# FRA_daughter_v2.net
KiCad netlist of a schematic drawn in EAGLE
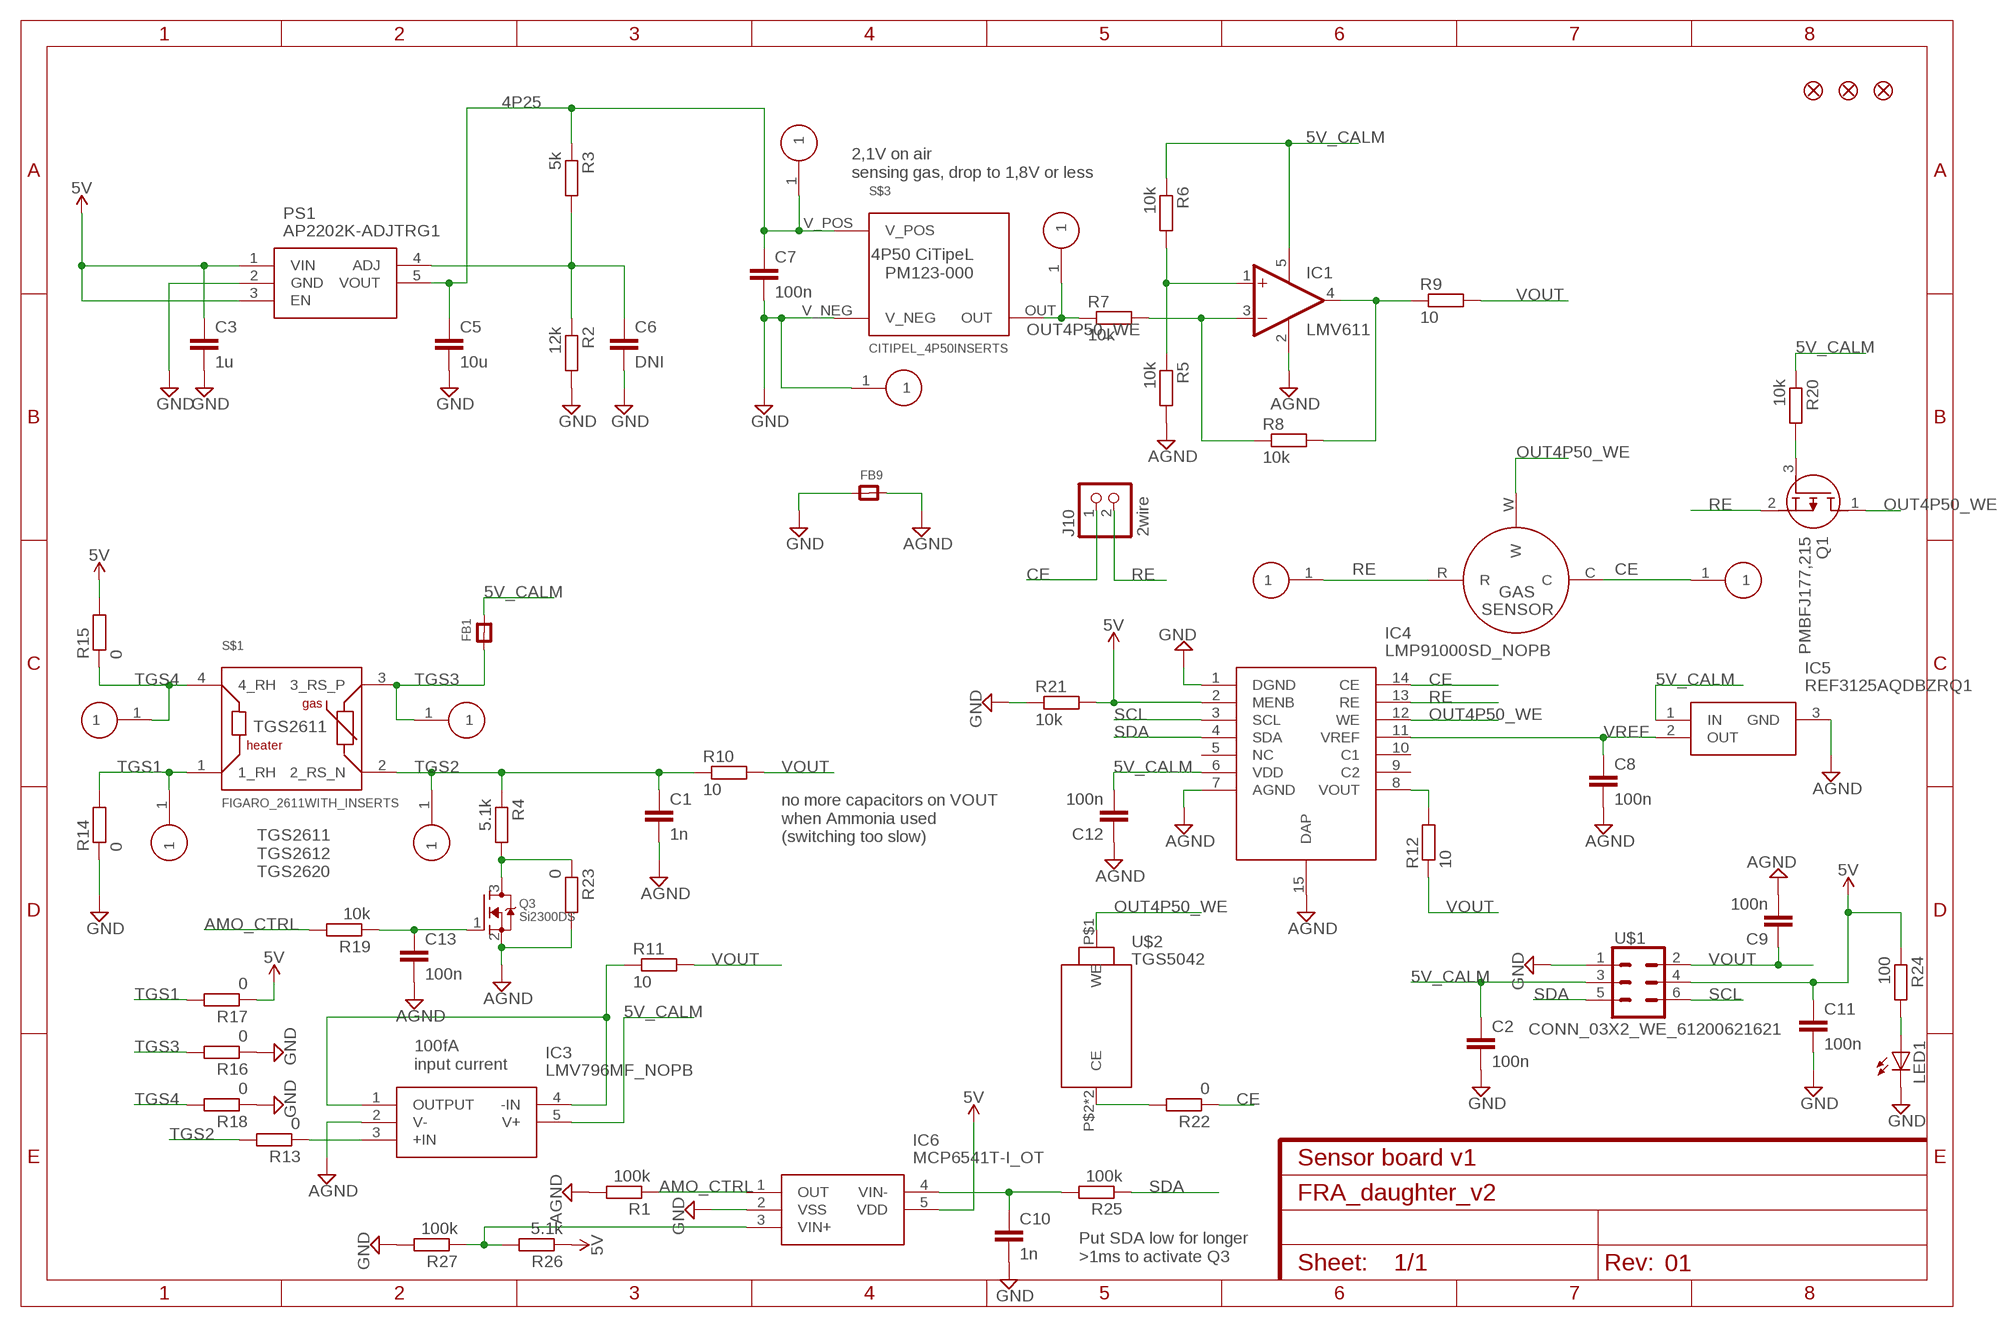
[diagram p0: schematic, sheet 1]

(export (version "E")
  (design (tool "Eeschema 10.0.6"))
  (components
    (comp (ref "C1")
      (value "1n")
      (footprint "eagle-import:C0603K")
      (libsource (lib "eagle-import") (part "C-EUC0603K"))
    )
    (comp (ref "C2")
      (value "100n")
      (footprint "eagle-import:C0603K")
      (libsource (lib "eagle-import") (part "C-EUC0603K"))
    )
    (comp (ref "C3")
      (value "1u")
      (footprint "eagle-import:C0603K")
      (libsource (lib "eagle-import") (part "C-EUC0603K"))
    )
    (comp (ref "C5")
      (value "10u")
      (footprint "eagle-import:C0603K")
      (libsource (lib "eagle-import") (part "C-EUC0603K"))
    )
    (comp (ref "C6")
      (value "DNI")
      (footprint "eagle-import:C0603K")
      (libsource (lib "eagle-import") (part "C-EUC0603K"))
    )
    (comp (ref "C7")
      (value "100n")
      (footprint "eagle-import:C0603K")
      (libsource (lib "eagle-import") (part "C-EUC0603K"))
    )
    (comp (ref "C8")
      (value "100n")
      (footprint "eagle-import:C0603K")
      (libsource (lib "eagle-import") (part "C-EUC0603K"))
    )
    (comp (ref "C9")
      (value "100n")
      (footprint "eagle-import:C0603K")
      (libsource (lib "eagle-import") (part "C-EUC0603K"))
    )
    (comp (ref "C10")
      (value "1n")
      (footprint "eagle-import:C0603K")
      (libsource (lib "eagle-import") (part "C-EUC0603K"))
    )
    (comp (ref "C11")
      (value "100n")
      (footprint "eagle-import:C0603K")
      (libsource (lib "eagle-import") (part "C-EUC0603K"))
    )
    (comp (ref "C12")
      (value "100n")
      (footprint "eagle-import:C0603K")
      (libsource (lib "eagle-import") (part "C-EUC0603K"))
    )
    (comp (ref "C13")
      (value "100n")
      (footprint "eagle-import:C0603K")
      (libsource (lib "eagle-import") (part "C-EUC0603K"))
    )
    (comp (ref "FB1")
      (value "FERRITE")
      (footprint "eagle-import:0603")
      (fields (field (name "PARTNO") "BLM18PG121SN1D"))
      (libsource (lib "eagle-import") (part "FERRITE"))
    )
    (comp (ref "FB9")
      (value "FERRITE")
      (footprint "eagle-import:0603")
      (fields (field (name "PARTNO") "BLM18PG121SN1D"))
      (libsource (lib "eagle-import") (part "FERRITE"))
    )
    (comp (ref "FID1")
      (value "FIDUCIAL\"\"")
      (footprint "eagle-import:FIDUCIAL_1MM")
      (libsource (lib "eagle-import") (part "FIDUCIAL{dblquote}{dblquote}"))
    )
    (comp (ref "FID2")
      (value "FIDUCIAL\"\"")
      (footprint "eagle-import:FIDUCIAL_1MM")
      (libsource (lib "eagle-import") (part "FIDUCIAL{dblquote}{dblquote}"))
    )
    (comp (ref "FID4")
      (value "FIDUCIAL\"\"")
      (footprint "eagle-import:FIDUCIAL_1MM")
      (libsource (lib "eagle-import") (part "FIDUCIAL{dblquote}{dblquote}"))
    )
    (comp (ref "IC1")
      (value "LMV611")
      (footprint "eagle-import:SC70-5L")
      (libsource (lib "eagle-import") (part "OPA333DCK"))
    )
    (comp (ref "IC3")
      (value "LMV796MF_NOPB")
      (footprint "eagle-import:SOT95P280X145-5N")
      (fields
        (field (name "MANUFACTURER_PART_NUMBER") "LMV796MF/NOPB")
        (field (name "MOUSER_PART_NUMBER") "926-LMV796MF/NOPB")
      )
      (libsource (lib "eagle-import") (part "LMV796MF_NOPB"))
    )
    (comp (ref "IC4")
      (value "LMP91000SD_NOPB")
      (footprint "eagle-import:SON50P400X400X80-15N")
      (fields
        (field (name "MANUFACTURER_PART_NUMBER") "LMP91000SD/NOPB")
        (field (name "MOUSER_PART_NUMBER") "926-LMP91000SD/NOPB")
      )
      (libsource (lib "eagle-import") (part "LMP91000SD_NOPB"))
    )
    (comp (ref "IC5")
      (value "REF3125AQDBZRQ1")
      (footprint "eagle-import:SOT95P237X112-3N")
      (fields (field (name "MOUSER_PART_NUMBER") "595-REF3125AQDBZRQ1"))
      (libsource (lib "eagle-import") (part "REF3125AQDBZRQ1"))
    )
    (comp (ref "IC6")
      (value "MCP6541T-I_OT")
      (footprint "eagle-import:SOT95P270X145-5N")
      (fields
        (field (name "MANUFACTURER_PART_NUMBER") "MCP6541T-I/OT")
        (field (name "MOUSER_PART_NUMBER") "579-MCP6541T-I/OT")
      )
      (libsource (lib "eagle-import") (part "MCP6541T-I_OT"))
    )
    (comp (ref "J1")
      (value "INSERT_MM5_06691.5MM")
      (footprint "eagle-import:INSERT_1MM5_9372")
      (libsource (lib "eagle-import") (part "INSERT_MM5_06691.5MM"))
    )
    (comp (ref "J2")
      (value "TGS3")
      (footprint "eagle-import:INSERT_MM5_0669")
      (libsource (lib "eagle-import") (part "INSERT_MM5_0669"))
    )
    (comp (ref "J3")
      (value "TGS2")
      (footprint "eagle-import:INSERT_MM5_0669")
      (libsource (lib "eagle-import") (part "INSERT_MM5_0669"))
    )
    (comp (ref "J4")
      (value "TGS1")
      (footprint "eagle-import:INSERT_MM5_0669")
      (libsource (lib "eagle-import") (part "INSERT_MM5_0669"))
    )
    (comp (ref "J5")
      (value "TGS4")
      (footprint "eagle-import:INSERT_MM5_0669")
      (libsource (lib "eagle-import") (part "INSERT_MM5_0669"))
    )
    (comp (ref "J6")
      (value "INSERT_MM5_06691.5MM")
      (footprint "eagle-import:INSERT_1MM5_9372")
      (libsource (lib "eagle-import") (part "INSERT_MM5_06691.5MM"))
    )
    (comp (ref "J7")
      (value "INSERT_MM5_06691.5MM")
      (footprint "eagle-import:INSERT_1MM5_9372")
      (libsource (lib "eagle-import") (part "INSERT_MM5_06691.5MM"))
    )
    (comp (ref "J8")
      (value "INSERT_MM5_06691.5MM")
      (footprint "eagle-import:INSERT_1MM5_9372")
      (libsource (lib "eagle-import") (part "INSERT_MM5_06691.5MM"))
    )
    (comp (ref "J9")
      (value "INSERT_MM5_06691.5MM")
      (footprint "eagle-import:INSERT_1MM5_9372")
      (libsource (lib "eagle-import") (part "INSERT_MM5_06691.5MM"))
    )
    (comp (ref "J10")
      (value "2wire")
      (footprint "eagle-import:1X02")
      (fields (field (name "PARTNO") "TSW-102-07-G-S"))
      (libsource (lib "eagle-import") (part "PINHD-1X2"))
    )
    (comp (ref "LED1")
      (value "LEDCHIP-LED0603")
      (footprint "eagle-import:CHIP-LED0603")
      (libsource (lib "eagle-import") (part "LEDCHIP-LED0603"))
    )
    (comp (ref "PS1")
      (value "AP2202K-ADJTRG1")
      (footprint "eagle-import:SOT95P280X145-5N")
      (fields (field (name "MOUSER_PART_NUMBER") "621-AP2202K-ADJTRG1"))
      (libsource (lib "eagle-import") (part "AP2202K-ADJTRG1"))
    )
    (comp (ref "Q1")
      (value "PMBFJ177,215")
      (footprint "eagle-import:SOT95P230X110-3N")
      (fields (field (name "MOUSER_PART_NUMBER") "771-PMBFJ177-T/R"))
      (libsource (lib "eagle-import") (part "PMBFJ177,215"))
    )
    (comp (ref "Q3")
      (value "Si2300DS")
      (footprint "eagle-import:SOT23")
      (libsource (lib "eagle-import") (part "MOSFET-NREFLOW"))
    )
    (comp (ref "R1")
      (value "100k")
      (footprint "eagle-import:R0603")
      (libsource (lib "eagle-import") (part "R-EU_R0603"))
    )
    (comp (ref "R2")
      (value "12k")
      (footprint "eagle-import:R0603")
      (libsource (lib "eagle-import") (part "R-EU_R0603"))
    )
    (comp (ref "R3")
      (value "5k")
      (footprint "eagle-import:R0603")
      (libsource (lib "eagle-import") (part "R-EU_R0603"))
    )
    (comp (ref "R4")
      (value "5.1k")
      (footprint "eagle-import:R0603")
      (libsource (lib "eagle-import") (part "R-EU_R0603"))
    )
    (comp (ref "R5")
      (value "10k")
      (footprint "eagle-import:R0603")
      (libsource (lib "eagle-import") (part "R-EU_R0603"))
    )
    (comp (ref "R6")
      (value "10k")
      (footprint "eagle-import:R0603")
      (libsource (lib "eagle-import") (part "R-EU_R0603"))
    )
    (comp (ref "R7")
      (value "10k")
      (footprint "eagle-import:R0603")
      (libsource (lib "eagle-import") (part "R-EU_R0603"))
    )
    (comp (ref "R8")
      (value "10k")
      (footprint "eagle-import:R0603")
      (libsource (lib "eagle-import") (part "R-EU_R0603"))
    )
    (comp (ref "R9")
      (value "10")
      (footprint "eagle-import:R0603")
      (libsource (lib "eagle-import") (part "R-EU_R0603"))
    )
    (comp (ref "R10")
      (value "10")
      (footprint "eagle-import:R0603")
      (libsource (lib "eagle-import") (part "R-EU_R0603"))
    )
    (comp (ref "R11")
      (value "10")
      (footprint "eagle-import:R0603")
      (libsource (lib "eagle-import") (part "R-EU_R0603"))
    )
    (comp (ref "R12")
      (value "10")
      (footprint "eagle-import:R0603")
      (libsource (lib "eagle-import") (part "R-EU_R0603"))
    )
    (comp (ref "R13")
      (value "0")
      (footprint "eagle-import:R0603")
      (libsource (lib "eagle-import") (part "R-EU_R0603"))
    )
    (comp (ref "R14")
      (value "0")
      (footprint "eagle-import:R0603")
      (libsource (lib "eagle-import") (part "R-EU_R0603"))
    )
    (comp (ref "R15")
      (value "0")
      (footprint "eagle-import:R0603")
      (libsource (lib "eagle-import") (part "R-EU_R0603"))
    )
    (comp (ref "R16")
      (value "0")
      (footprint "eagle-import:R0603")
      (libsource (lib "eagle-import") (part "R-EU_R0603"))
    )
    (comp (ref "R17")
      (value "0")
      (footprint "eagle-import:R0603")
      (libsource (lib "eagle-import") (part "R-EU_R0603"))
    )
    (comp (ref "R18")
      (value "0")
      (footprint "eagle-import:R0603")
      (libsource (lib "eagle-import") (part "R-EU_R0603"))
    )
    (comp (ref "R19")
      (value "10k")
      (footprint "eagle-import:R0603")
      (libsource (lib "eagle-import") (part "R-EU_R0603"))
    )
    (comp (ref "R20")
      (value "10k")
      (footprint "eagle-import:R0603")
      (libsource (lib "eagle-import") (part "R-EU_R0603"))
    )
    (comp (ref "R21")
      (value "10k")
      (footprint "eagle-import:R0603")
      (libsource (lib "eagle-import") (part "R-EU_R0603"))
    )
    (comp (ref "R22")
      (value "0")
      (footprint "eagle-import:R0603")
      (libsource (lib "eagle-import") (part "R-EU_R0603"))
    )
    (comp (ref "R23")
      (value "0")
      (footprint "eagle-import:R0603")
      (libsource (lib "eagle-import") (part "R-EU_R0603"))
    )
    (comp (ref "R24")
      (value "100")
      (footprint "eagle-import:R0603")
      (libsource (lib "eagle-import") (part "R-EU_R0603"))
    )
    (comp (ref "R25")
      (value "100k")
      (footprint "eagle-import:R0603")
      (libsource (lib "eagle-import") (part "R-EU_R0603"))
    )
    (comp (ref "R26")
      (value "5.1k")
      (footprint "eagle-import:R0603")
      (libsource (lib "eagle-import") (part "R-EU_R0603"))
    )
    (comp (ref "R27")
      (value "100k")
      (footprint "eagle-import:R0603")
      (libsource (lib "eagle-import") (part "R-EU_R0603"))
    )
    (comp (ref "S$1")
      (value "FIGARO_2611WITH_INSERTS")
      (footprint "eagle-import:TH4_TGS2611_INSERTS")
      (libsource (lib "eagle-import") (part "FIGARO_2611WITH_INSERTS"))
    )
    (comp (ref "S$3")
      (value "CITIPEL_4P50INSERTS")
      (footprint "eagle-import:TH3_4P50_INSERTS")
      (libsource (lib "eagle-import") (part "CITIPEL_4P50INSERTS"))
    )
    (comp (ref "U$1")
      (value "CONN_03X2_WE_61200621621")
      (footprint "eagle-import:WE_61200621621")
      (libsource (lib "eagle-import") (part "CONN_03X2_WE_61200621621"))
    )
    (comp (ref "U$2")
      (value "TGS5042")
      (footprint "eagle-import:TGS5042")
      (libsource (lib "eagle-import") (part "TGS5042"))
    )
    (comp (ref "X1")
      (value "3-ELECTRODE-GAS-SENSORINS")
      (footprint "eagle-import:3-ELECTRODE_INSETRS")
      (libsource (lib "eagle-import") (part "3-ELECTRODE-GAS-SENSORINS"))
    )
  )
  (nets
    (net (code "1") (name "/4P25") (class "Default")
      (node (ref "C5") (pin "1") (pinfunction "1_1") (pintype "passive"))
      (node (ref "C7") (pin "1") (pinfunction "1_1") (pintype "passive"))
      (node (ref "J6") (pin "1") (pinfunction "1_1") (pintype "bidirectional"))
      (node (ref "PS1") (pin "5") (pinfunction "VOUT_5") (pintype "power_in"))
      (node (ref "R3") (pin "1") (pinfunction "1_1") (pintype "passive"))
      (node (ref "S$3") (pin "V_POS") (pinfunction "V_POS_V_POS") (pintype "power_in"))
    )
    (net (code "2") (name "/5V_CALM") (class "Default")
      (node (ref "C12") (pin "2") (pinfunction "2_2") (pintype "passive"))
      (node (ref "C2") (pin "1") (pinfunction "1_1") (pintype "passive"))
      (node (ref "FB1") (pin "2") (pinfunction "P$2_2") (pintype "passive"))
      (node (ref "IC1") (pin "5") (pinfunction "V+_5") (pintype "power_in"))
      (node (ref "IC3") (pin "5") (pinfunction "V+_5") (pintype "bidirectional"))
      (node (ref "IC4") (pin "6") (pinfunction "VDD_6") (pintype "power_in"))
      (node (ref "IC5") (pin "1") (pinfunction "IN_1") (pintype "bidirectional"))
      (node (ref "R20") (pin "1") (pinfunction "1_1") (pintype "passive"))
      (node (ref "R6") (pin "1") (pinfunction "1_1") (pintype "passive"))
      (node (ref "U$1") (pin "3") (pinfunction "3_3") (pintype "bidirectional"))
    )
    (net (code "3") (name "/AMO_CTRL") (class "Default")
      (node (ref "IC6") (pin "1") (pinfunction "OUT_1") (pintype "output"))
      (node (ref "R1") (pin "1") (pinfunction "1_1") (pintype "passive"))
      (node (ref "R19") (pin "2") (pinfunction "2_2") (pintype "passive"))
    )
    (net (code "4") (name "/CE") (class "Default")
      (node (ref "IC4") (pin "14") (pinfunction "CE_14") (pintype "input"))
      (node (ref "J10") (pin "1") (pinfunction "1_1") (pintype "passive"))
      (node (ref "J9") (pin "1") (pinfunction "1_1") (pintype "bidirectional"))
      (node (ref "R22") (pin "1") (pinfunction "1_1") (pintype "passive"))
      (node (ref "X1") (pin "C") (pinfunction "C_C") (pintype "bidirectional"))
    )
    (net (code "5") (name "/OUT4P50_WE") (class "Default")
      (node (ref "IC4") (pin "12") (pinfunction "WE_12") (pintype "input"))
      (node (ref "J7") (pin "1") (pinfunction "1_1") (pintype "bidirectional"))
      (node (ref "Q1") (pin "1") (pinfunction "D_1") (pintype "bidirectional"))
      (node (ref "R7") (pin "1") (pinfunction "1_1") (pintype "passive"))
      (node (ref "S$3") (pin "OUT") (pinfunction "OUT_OUT") (pintype "bidirectional"))
      (node (ref "U$2") (pin "P$1") (pinfunction "WE_P$1") (pintype "bidirectional"))
      (node (ref "X1") (pin "W") (pinfunction "W_W") (pintype "bidirectional"))
    )
    (net (code "6") (name "/RE") (class "Default")
      (node (ref "IC4") (pin "13") (pinfunction "RE_13") (pintype "input"))
      (node (ref "J10") (pin "2") (pinfunction "2_2") (pintype "passive"))
      (node (ref "J8") (pin "1") (pinfunction "1_1") (pintype "bidirectional"))
      (node (ref "Q1") (pin "2") (pinfunction "S_2") (pintype "bidirectional"))
      (node (ref "X1") (pin "R") (pinfunction "R_R") (pintype "bidirectional"))
    )
    (net (code "7") (name "/SCL") (class "Default")
      (node (ref "IC4") (pin "3") (pinfunction "SCL_3") (pintype "input"))
      (node (ref "U$1") (pin "6") (pinfunction "6_6") (pintype "bidirectional"))
    )
    (net (code "8") (name "/SDA") (class "Default")
      (node (ref "IC4") (pin "4") (pinfunction "SDA_4") (pintype "bidirectional"))
      (node (ref "R25") (pin "1") (pinfunction "1_1") (pintype "passive"))
      (node (ref "U$1") (pin "5") (pinfunction "5_5") (pintype "bidirectional"))
    )
    (net (code "9") (name "/TGS1") (class "Default")
      (node (ref "J4") (pin "1") (pinfunction "1_1") (pintype "bidirectional"))
      (node (ref "R14") (pin "2") (pinfunction "2_2") (pintype "passive"))
      (node (ref "R17") (pin "2") (pinfunction "2_2") (pintype "passive"))
      (node (ref "S$1") (pin "1") (pinfunction "1_RH_1") (pintype "bidirectional"))
    )
    (net (code "10") (name "/TGS2") (class "Default")
      (node (ref "C1") (pin "1") (pinfunction "1_1") (pintype "passive"))
      (node (ref "J3") (pin "1") (pinfunction "1_1") (pintype "bidirectional"))
      (node (ref "R10") (pin "1") (pinfunction "1_1") (pintype "passive"))
      (node (ref "R13") (pin "2") (pinfunction "2_2") (pintype "passive"))
      (node (ref "R4") (pin "1") (pinfunction "1_1") (pintype "passive"))
      (node (ref "S$1") (pin "2") (pinfunction "2_RS_N_2") (pintype "bidirectional"))
    )
    (net (code "11") (name "/TGS3") (class "Default")
      (node (ref "FB1") (pin "1") (pinfunction "P$1_1") (pintype "passive"))
      (node (ref "J2") (pin "1") (pinfunction "1_1") (pintype "bidirectional"))
      (node (ref "R16") (pin "2") (pinfunction "2_2") (pintype "passive"))
      (node (ref "S$1") (pin "3") (pinfunction "3_RS_P_3") (pintype "bidirectional"))
    )
    (net (code "12") (name "/TGS4") (class "Default")
      (node (ref "J5") (pin "1") (pinfunction "1_1") (pintype "bidirectional"))
      (node (ref "R15") (pin "1") (pinfunction "1_1") (pintype "passive"))
      (node (ref "R18") (pin "2") (pinfunction "2_2") (pintype "passive"))
      (node (ref "S$1") (pin "4") (pinfunction "4_RH_4") (pintype "bidirectional"))
    )
    (net (code "13") (name "/VOUT") (class "Default")
      (node (ref "C9") (pin "1") (pinfunction "1_1") (pintype "passive"))
      (node (ref "R10") (pin "2") (pinfunction "2_2") (pintype "passive"))
      (node (ref "R11") (pin "2") (pinfunction "2_2") (pintype "passive"))
      (node (ref "R12") (pin "1") (pinfunction "1_1") (pintype "passive"))
      (node (ref "R9") (pin "2") (pinfunction "2_2") (pintype "passive"))
      (node (ref "U$1") (pin "2") (pinfunction "2_2") (pintype "bidirectional"))
    )
    (net (code "14") (name "/VREF") (class "Default")
      (node (ref "C8") (pin "1") (pinfunction "1_1") (pintype "passive"))
      (node (ref "IC4") (pin "11") (pinfunction "VREF_11") (pintype "input"))
      (node (ref "IC5") (pin "2") (pinfunction "OUT_2") (pintype "bidirectional"))
    )
    (net (code "15") (name "5V") (class "Default")
      (node (ref "C11") (pin "1") (pinfunction "1_1") (pintype "passive"))
      (node (ref "C3") (pin "1") (pinfunction "1_1") (pintype "passive"))
      (node (ref "IC4") (pin "2") (pinfunction "MENB_2") (pintype "input"))
      (node (ref "IC6") (pin "5") (pinfunction "VDD_5") (pintype "power_in"))
      (node (ref "PS1") (pin "1") (pinfunction "VIN_1") (pintype "power_in"))
      (node (ref "PS1") (pin "3") (pinfunction "EN_3") (pintype "input"))
      (node (ref "R15") (pin "2") (pinfunction "2_2") (pintype "passive"))
      (node (ref "R17") (pin "1") (pinfunction "1_1") (pintype "passive"))
      (node (ref "R21") (pin "2") (pinfunction "2_2") (pintype "passive"))
      (node (ref "R24") (pin "1") (pinfunction "1_1") (pintype "passive"))
      (node (ref "R26") (pin "1") (pinfunction "1_1") (pintype "passive"))
      (node (ref "U$1") (pin "4") (pinfunction "4_4") (pintype "bidirectional"))
    )
    (net (code "16") (name "AGND") (class "Default")
      (node (ref "C1") (pin "2") (pinfunction "2_2") (pintype "passive"))
      (node (ref "C12") (pin "1") (pinfunction "1_1") (pintype "passive"))
      (node (ref "C13") (pin "2") (pinfunction "2_2") (pintype "passive"))
      (node (ref "C8") (pin "2") (pinfunction "2_2") (pintype "passive"))
      (node (ref "C9") (pin "2") (pinfunction "2_2") (pintype "passive"))
      (node (ref "FB9") (pin "2") (pinfunction "P$2_2") (pintype "passive"))
      (node (ref "IC1") (pin "2") (pinfunction "V-_2") (pintype "power_in"))
      (node (ref "IC3") (pin "2") (pinfunction "V-_2") (pintype "bidirectional"))
      (node (ref "IC4") (pin "15") (pinfunction "DAP_15") (pintype "power_in"))
      (node (ref "IC4") (pin "7") (pinfunction "AGND_7") (pintype "power_in"))
      (node (ref "IC5") (pin "3") (pinfunction "GND_3") (pintype "bidirectional"))
      (node (ref "Q3") (pin "2") (pinfunction "S_2") (pintype "bidirectional"))
      (node (ref "R1") (pin "2") (pinfunction "2_2") (pintype "passive"))
      (node (ref "R23") (pin "2") (pinfunction "2_2") (pintype "passive"))
      (node (ref "R5") (pin "2") (pinfunction "2_2") (pintype "passive"))
    )
    (net (code "17") (name "GND") (class "Default")
      (node (ref "C10") (pin "2") (pinfunction "2_2") (pintype "passive"))
      (node (ref "C11") (pin "2") (pinfunction "2_2") (pintype "passive"))
      (node (ref "C2") (pin "2") (pinfunction "2_2") (pintype "passive"))
      (node (ref "C3") (pin "2") (pinfunction "2_2") (pintype "passive"))
      (node (ref "C5") (pin "2") (pinfunction "2_2") (pintype "passive"))
      (node (ref "C6") (pin "2") (pinfunction "2_2") (pintype "passive"))
      (node (ref "C7") (pin "2") (pinfunction "2_2") (pintype "passive"))
      (node (ref "FB9") (pin "1") (pinfunction "P$1_1") (pintype "passive"))
      (node (ref "IC4") (pin "1") (pinfunction "DGND_1") (pintype "power_in"))
      (node (ref "IC6") (pin "2") (pinfunction "VSS_2") (pintype "power_in"))
      (node (ref "J1") (pin "1") (pinfunction "1_1") (pintype "bidirectional"))
      (node (ref "LED1") (pin "C") (pinfunction "C_C") (pintype "passive"))
      (node (ref "PS1") (pin "2") (pinfunction "GND_2") (pintype "power_in"))
      (node (ref "R14") (pin "1") (pinfunction "1_1") (pintype "passive"))
      (node (ref "R16") (pin "1") (pinfunction "1_1") (pintype "passive"))
      (node (ref "R18") (pin "1") (pinfunction "1_1") (pintype "passive"))
      (node (ref "R2") (pin "2") (pinfunction "2_2") (pintype "passive"))
      (node (ref "R21") (pin "1") (pinfunction "1_1") (pintype "passive"))
      (node (ref "R27") (pin "2") (pinfunction "2_2") (pintype "passive"))
      (node (ref "S$3") (pin "V_NEG") (pinfunction "V_NEG_V_NEG") (pintype "power_in"))
      (node (ref "U$1") (pin "1") (pinfunction "1_1") (pintype "bidirectional"))
    )
    (net (code "18") (name "Net-(IC1-+IN)") (class "Default")
      (node (ref "IC1") (pin "1") (pinfunction "+IN_1") (pintype "input"))
      (node (ref "R5") (pin "1") (pinfunction "1_1") (pintype "passive"))
      (node (ref "R6") (pin "2") (pinfunction "2_2") (pintype "passive"))
    )
    (net (code "19") (name "Net-(IC1--IN)") (class "Default")
      (node (ref "IC1") (pin "3") (pinfunction "-IN_3") (pintype "input"))
      (node (ref "R7") (pin "2") (pinfunction "2_2") (pintype "passive"))
      (node (ref "R8") (pin "1") (pinfunction "1_1") (pintype "passive"))
    )
    (net (code "20") (name "Net-(IC1-OUT)") (class "Default")
      (node (ref "IC1") (pin "4") (pinfunction "OUT_4") (pintype "output"))
      (node (ref "R8") (pin "2") (pinfunction "2_2") (pintype "passive"))
      (node (ref "R9") (pin "1") (pinfunction "1_1") (pintype "passive"))
    )
    (net (code "21") (name "Net-(IC3-+IN)") (class "Default")
      (node (ref "IC3") (pin "3") (pinfunction "+IN_3") (pintype "input"))
      (node (ref "R13") (pin "1") (pinfunction "1_1") (pintype "passive"))
    )
    (net (code "22") (name "Net-(IC3--IN)") (class "Default")
      (node (ref "IC3") (pin "1") (pinfunction "OUTPUT_1") (pintype "output"))
      (node (ref "IC3") (pin "4") (pinfunction "-IN_4") (pintype "input"))
      (node (ref "R11") (pin "1") (pinfunction "1_1") (pintype "passive"))
    )
    (net (code "23") (name "Net-(IC4-VOUT)") (class "Default")
      (node (ref "IC4") (pin "8") (pinfunction "VOUT_8") (pintype "output"))
      (node (ref "R12") (pin "2") (pinfunction "2_2") (pintype "passive"))
    )
    (net (code "24") (name "Net-(IC6-VIN+)") (class "Default")
      (node (ref "IC6") (pin "3") (pinfunction "VIN+_3") (pintype "input"))
      (node (ref "R26") (pin "2") (pinfunction "2_2") (pintype "passive"))
      (node (ref "R27") (pin "1") (pinfunction "1_1") (pintype "passive"))
    )
    (net (code "25") (name "Net-(IC6-VIN-)") (class "Default")
      (node (ref "C10") (pin "1") (pinfunction "1_1") (pintype "passive"))
      (node (ref "IC6") (pin "4") (pinfunction "VIN-_4") (pintype "input"))
      (node (ref "R25") (pin "2") (pinfunction "2_2") (pintype "passive"))
    )
    (net (code "26") (name "Net-(LED1-PadA)") (class "Default")
      (node (ref "LED1") (pin "A") (pinfunction "A_A") (pintype "passive"))
      (node (ref "R24") (pin "2") (pinfunction "2_2") (pintype "passive"))
    )
    (net (code "27") (name "Net-(PS1-ADJ)") (class "Default")
      (node (ref "C6") (pin "1") (pinfunction "1_1") (pintype "passive"))
      (node (ref "PS1") (pin "4") (pinfunction "ADJ_4") (pintype "bidirectional"))
      (node (ref "R2") (pin "1") (pinfunction "1_1") (pintype "passive"))
      (node (ref "R3") (pin "2") (pinfunction "2_2") (pintype "passive"))
    )
    (net (code "28") (name "Net-(Q1-G)") (class "Default")
      (node (ref "Q1") (pin "3") (pinfunction "G_3") (pintype "bidirectional"))
      (node (ref "R20") (pin "2") (pinfunction "2_2") (pintype "passive"))
    )
    (net (code "29") (name "Net-(Q3-D)") (class "Default")
      (node (ref "Q3") (pin "3") (pinfunction "D_3") (pintype "bidirectional"))
      (node (ref "R23") (pin "1") (pinfunction "1_1") (pintype "passive"))
      (node (ref "R4") (pin "2") (pinfunction "2_2") (pintype "passive"))
    )
    (net (code "30") (name "Net-(Q3-G)") (class "Default")
      (node (ref "C13") (pin "1") (pinfunction "1_1") (pintype "passive"))
      (node (ref "Q3") (pin "1") (pinfunction "G_1") (pintype "bidirectional"))
      (node (ref "R19") (pin "1") (pinfunction "1_1") (pintype "passive"))
    )
    (net (code "31") (name "Net-(R22-Pad2)") (class "Default")
      (node (ref "R22") (pin "2") (pinfunction "2_2") (pintype "passive"))
      (node (ref "U$2") (pin "P$2") (pinfunction "CE_P$2") (pintype "bidirectional"))
      (node (ref "U$2") (pin "P$3") (pinfunction "CE_P$3") (pintype "bidirectional"))
    )
    (net (code "32") (name "unconnected-(IC4-C1-Pad10)") (class "Default")
      (node (ref "IC4") (pin "10") (pinfunction "C1_10") (pintype "bidirectional"))
    )
    (net (code "33") (name "unconnected-(IC4-C2-Pad9)") (class "Default")
      (node (ref "IC4") (pin "9") (pinfunction "C2_9") (pintype "bidirectional"))
    )
    (net (code "34") (name "unconnected-(IC4-NC-Pad5)") (class "Default")
      (node (ref "IC4") (pin "5") (pinfunction "NC_5") (pintype "no_connect"))
    )
  )
)
